# BMD_RevB_B2_TX.net
KiCad netlist of a schematic drawn in Altium Designer
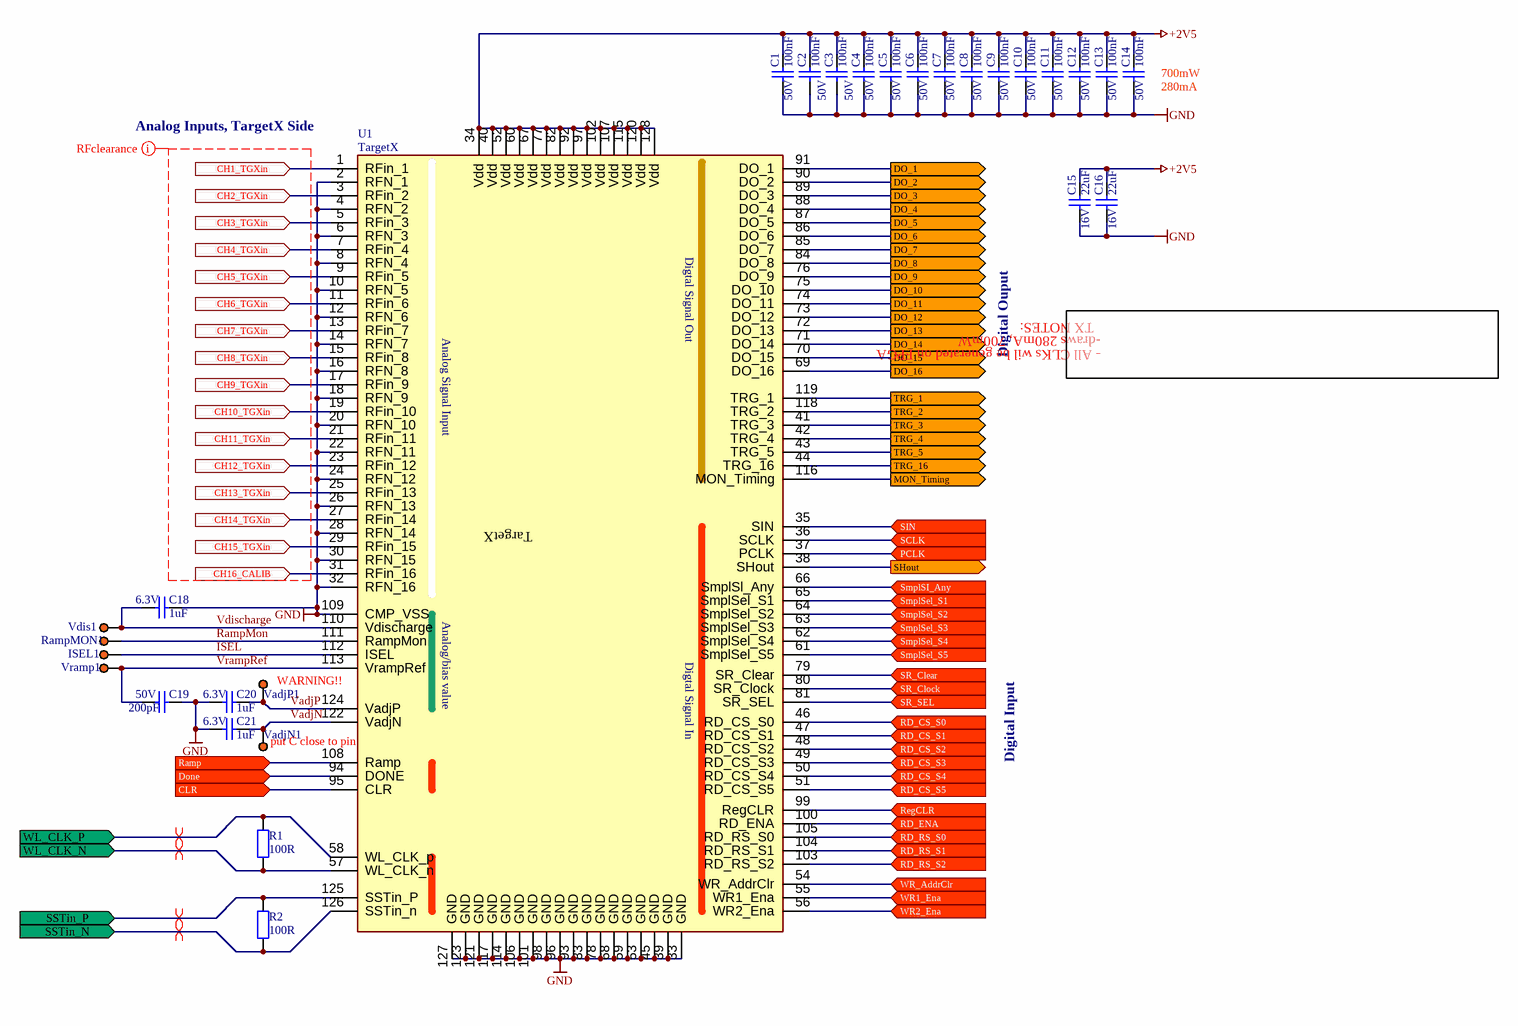
[diagram p0: BMD_RevB_B2_TX.SchDoc]

(export (version "E")
  (design (tool "Eeschema 10.0.6"))
  (components
    (comp (ref "C1")
      (value "100nF")
      (footprint "CC0402N1R")
      (description "0.10µF 50V Ceramic Capacitor X7R 0402")
      (fields (field (name "MANUFACTURER") "TDK") (field (name "VOLTAGE RATING") "50V"))
      (libsource (lib "BMD") (part "CAPCC0402_100N_50VX7R"))
    )
    (comp (ref "C2")
      (value "100nF")
      (footprint "CC0402N1R")
      (description "0.10µF 50V Ceramic Capacitor X7R 0402")
      (fields (field (name "MANUFACTURER") "TDK") (field (name "VOLTAGE RATING") "50V"))
      (libsource (lib "BMD") (part "CAPCC0402_100N_50VX7R"))
    )
    (comp (ref "C3")
      (value "100nF")
      (footprint "CC0402N1R")
      (description "0.10µF 50V Ceramic Capacitor X7R 0402")
      (fields (field (name "MANUFACTURER") "TDK") (field (name "VOLTAGE RATING") "50V"))
      (libsource (lib "BMD") (part "CAPCC0402_100N_50VX7R"))
    )
    (comp (ref "C4")
      (value "100nF")
      (footprint "CC0402N1R")
      (description "0.10µF 50V Ceramic Capacitor X7R 0402")
      (fields (field (name "MANUFACTURER") "TDK") (field (name "VOLTAGE RATING") "50V"))
      (libsource (lib "BMD") (part "CAPCC0402_100N_50VX7R"))
    )
    (comp (ref "C5")
      (value "100nF")
      (footprint "CC0402N1R")
      (description "0.10µF 50V Ceramic Capacitor X7R 0402")
      (fields (field (name "MANUFACTURER") "TDK") (field (name "VOLTAGE RATING") "50V"))
      (libsource (lib "BMD") (part "CAPCC0402_100N_50VX7R"))
    )
    (comp (ref "C6")
      (value "100nF")
      (footprint "CC0402N1R")
      (description "0.10µF 50V Ceramic Capacitor X7R 0402")
      (fields (field (name "MANUFACTURER") "TDK") (field (name "VOLTAGE RATING") "50V"))
      (libsource (lib "BMD") (part "CAPCC0402_100N_50VX7R"))
    )
    (comp (ref "C7")
      (value "100nF")
      (footprint "CC0402N1R")
      (description "0.10µF 50V Ceramic Capacitor X7R 0402")
      (fields (field (name "MANUFACTURER") "TDK") (field (name "VOLTAGE RATING") "50V"))
      (libsource (lib "BMD") (part "CAPCC0402_100N_50VX7R"))
    )
    (comp (ref "C8")
      (value "100nF")
      (footprint "CC0402N1R")
      (description "0.10µF 50V Ceramic Capacitor X7R 0402")
      (fields (field (name "MANUFACTURER") "TDK") (field (name "VOLTAGE RATING") "50V"))
      (libsource (lib "BMD") (part "CAPCC0402_100N_50VX7R"))
    )
    (comp (ref "C9")
      (value "100nF")
      (footprint "CC0402N1R")
      (description "0.10µF 50V Ceramic Capacitor X7R 0402")
      (fields (field (name "MANUFACTURER") "TDK") (field (name "VOLTAGE RATING") "50V"))
      (libsource (lib "BMD") (part "CAPCC0402_100N_50VX7R"))
    )
    (comp (ref "C10")
      (value "100nF")
      (footprint "CC0402N1R")
      (description "0.10µF 50V Ceramic Capacitor X7R 0402")
      (fields (field (name "MANUFACTURER") "TDK") (field (name "VOLTAGE RATING") "50V"))
      (libsource (lib "BMD") (part "CAPCC0402_100N_50VX7R"))
    )
    (comp (ref "C11")
      (value "100nF")
      (footprint "CC0402N1R")
      (description "0.10µF 50V Ceramic Capacitor X7R 0402")
      (fields (field (name "MANUFACTURER") "TDK") (field (name "VOLTAGE RATING") "50V"))
      (libsource (lib "BMD") (part "CAPCC0402_100N_50VX7R"))
    )
    (comp (ref "C12")
      (value "100nF")
      (footprint "CC0402N1R")
      (description "0.10µF 50V Ceramic Capacitor X7R 0402")
      (fields (field (name "MANUFACTURER") "TDK") (field (name "VOLTAGE RATING") "50V"))
      (libsource (lib "BMD") (part "CAPCC0402_100N_50VX7R"))
    )
    (comp (ref "C13")
      (value "100nF")
      (footprint "CC0402N1R")
      (description "0.10µF 50V Ceramic Capacitor X7R 0402")
      (fields (field (name "MANUFACTURER") "TDK") (field (name "VOLTAGE RATING") "50V"))
      (libsource (lib "BMD") (part "CAPCC0402_100N_50VX7R"))
    )
    (comp (ref "C14")
      (value "100nF")
      (footprint "CC0402N1R")
      (description "0.10µF 50V Ceramic Capacitor X7R 0402")
      (fields (field (name "MANUFACTURER") "TDK") (field (name "VOLTAGE RATING") "50V"))
      (libsource (lib "BMD") (part "CAPCC0402_100N_50VX7R"))
    )
    (comp (ref "C15")
      (value "22uF")
      (footprint "CC0805N1R")
      (description "22µF 16V Ceramic Capacitor X5R 0805")
      (fields (field (name "MANUFACTURER") "Murata") (field (name "VOLTAGE RATING") "16V"))
      (libsource (lib "BMD") (part "CAPCC0805_22U_16VX7R"))
    )
    (comp (ref "C16")
      (value "22uF")
      (footprint "CC0805N1R")
      (description "22µF 16V Ceramic Capacitor X5R 0805")
      (fields (field (name "MANUFACTURER") "Murata") (field (name "VOLTAGE RATING") "16V"))
      (libsource (lib "BMD") (part "CAPCC0805_22U_16VX7R"))
    )
    (comp (ref "C18")
      (value "1uF")
      (footprint "CC0402N1R")
      (description "1µF 6.3V Ceramic Capacitor X7R 0402")
      (fields (field (name "MANUFACTURER") "TDK") (field (name "VOLTAGE RATING") "6.3V"))
      (libsource (lib "BMD") (part "CAPCC0402_1.0U_50VX7R"))
    )
    (comp (ref "C19")
      (value "200pF")
      (footprint "CC0402N1R")
      (description "Capacitor chip ceramic 0402 50V NPO")
      (fields (field (name "MANUFACTURER") "Murata") (field (name "VOLTAGE RATING") "50V"))
      (libsource (lib "BMD") (part "CAPCC0402_200P_50VNP0"))
    )
    (comp (ref "C20")
      (value "1uF")
      (footprint "CC0402N1R")
      (description "1µF 6.3V Ceramic Capacitor X7R 0402")
      (fields (field (name "MANUFACTURER") "TDK") (field (name "VOLTAGE RATING") "6.3V"))
      (libsource (lib "BMD") (part "CAPCC0402_1.0U_50VX7R"))
    )
    (comp (ref "C21")
      (value "1uF")
      (footprint "CC0402N1R")
      (description "1µF 6.3V Ceramic Capacitor X7R 0402")
      (fields (field (name "MANUFACTURER") "TDK") (field (name "VOLTAGE RATING") "6.3V"))
      (libsource (lib "BMD") (part "CAPCC0402_1.0U_50VX7R"))
    )
    (comp (ref "ISEL1")
      (value "SP1.5S")
      (footprint "SP1.5SQ")
      (description "Wire solder pin 1.5mm")
      (libsource (lib "Connectors_Old") (part "SP1.5S"))
    )
    (comp (ref "R1")
      (value "100R")
      (footprint "RC0402N1R")
      (description "RES SMD 100 OHM 1% 1/10W 0402")
      (fields (field (name "MANUFACTURER") "Panasonic"))
      (libsource (lib "BMD") (part "RES0402-100R-1%100PPM"))
    )
    (comp (ref "R2")
      (value "100R")
      (footprint "RC0402N1R")
      (description "RES SMD 100 OHM 1% 1/10W 0402")
      (fields (field (name "MANUFACTURER") "Panasonic"))
      (libsource (lib "BMD") (part "RES0402-100R-1%100PPM"))
    )
    (comp (ref "RampMON1")
      (value "SP1.5S")
      (footprint "SP1.5SQ")
      (description "Wire solder pin 1.5mm")
      (libsource (lib "Connectors_Old") (part "SP1.5S"))
    )
    (comp (ref "U1")
      (value "TargetX")
      (footprint "TQFP128_MZA")
      (description "16-channel, 1GSPS Transient Waveform Recorder")
      (fields (field (name "MANUFACTURER") "UHM_IDL"))
      (libsource (lib "IDlab") (part "DIGITZ_TargetX"))
    )
    (comp (ref "VadjN1")
      (value "SP1.5S")
      (footprint "SP1.5SQ")
      (description "Wire solder pin 1.5mm")
      (libsource (lib "Connectors_Old") (part "SP1.5S"))
    )
    (comp (ref "VadjP1")
      (value "SP1.5S")
      (footprint "SP1.5SQ")
      (description "Wire solder pin 1.5mm")
      (libsource (lib "Connectors_Old") (part "SP1.5S"))
    )
    (comp (ref "Vdis1")
      (value "SP1.5S")
      (footprint "SP1.5SQ")
      (description "Wire solder pin 1.5mm")
      (libsource (lib "Connectors_Old") (part "SP1.5S"))
    )
    (comp (ref "Vramp1")
      (value "SP1.5S")
      (footprint "SP1.5SQ")
      (description "Wire solder pin 1.5mm")
      (libsource (lib "Connectors_Old") (part "SP1.5S"))
    )
  )
  (nets
    (net (code "1") (name "+2V5") (class "Default")
      (node (ref "C1") (pin "2") (pinfunction "2_2") (pintype "passive"))
      (node (ref "C10") (pin "2") (pinfunction "2_2") (pintype "passive"))
      (node (ref "C11") (pin "2") (pinfunction "2_2") (pintype "passive"))
      (node (ref "C12") (pin "2") (pinfunction "2_2") (pintype "passive"))
      (node (ref "C13") (pin "2") (pinfunction "2_2") (pintype "passive"))
      (node (ref "C14") (pin "2") (pinfunction "2_2") (pintype "passive"))
      (node (ref "C15") (pin "2") (pinfunction "2_2") (pintype "passive"))
      (node (ref "C16") (pin "2") (pinfunction "2_2") (pintype "passive"))
      (node (ref "C2") (pin "2") (pinfunction "2_2") (pintype "passive"))
      (node (ref "C3") (pin "2") (pinfunction "2_2") (pintype "passive"))
      (node (ref "C4") (pin "2") (pinfunction "2_2") (pintype "passive"))
      (node (ref "C5") (pin "2") (pinfunction "2_2") (pintype "passive"))
      (node (ref "C6") (pin "2") (pinfunction "2_2") (pintype "passive"))
      (node (ref "C7") (pin "2") (pinfunction "2_2") (pintype "passive"))
      (node (ref "C8") (pin "2") (pinfunction "2_2") (pintype "passive"))
      (node (ref "C9") (pin "2") (pinfunction "2_2") (pintype "passive"))
      (node (ref "U1") (pin "102") (pinfunction "Vdd_102") (pintype "passive"))
      (node (ref "U1") (pin "107") (pinfunction "Vdd_107") (pintype "passive"))
      (node (ref "U1") (pin "115") (pinfunction "Vdd_115") (pintype "passive"))
      (node (ref "U1") (pin "120") (pinfunction "Vdd_120") (pintype "passive"))
      (node (ref "U1") (pin "128") (pinfunction "Vdd_128") (pintype "passive"))
      (node (ref "U1") (pin "34") (pinfunction "Vdd_34") (pintype "passive"))
      (node (ref "U1") (pin "40") (pinfunction "Vdd_40") (pintype "passive"))
      (node (ref "U1") (pin "52") (pinfunction "Vdd_52") (pintype "passive"))
      (node (ref "U1") (pin "60") (pinfunction "Vdd_60") (pintype "passive"))
      (node (ref "U1") (pin "67") (pinfunction "Vdd_67") (pintype "passive"))
      (node (ref "U1") (pin "77") (pinfunction "Vdd_77") (pintype "passive"))
      (node (ref "U1") (pin "82") (pinfunction "Vdd_82") (pintype "passive"))
      (node (ref "U1") (pin "92") (pinfunction "Vdd_92") (pintype "passive"))
      (node (ref "U1") (pin "97") (pinfunction "Vdd_97") (pintype "passive"))
    )
    (net (code "2") (name "/CH1_TGXin") (class "Default")
      (node (ref "U1") (pin "1") (pinfunction "RFin_1_1") (pintype "passive"))
    )
    (net (code "3") (name "/CH2_TGXin") (class "Default")
      (node (ref "U1") (pin "3") (pinfunction "RFin_2_3") (pintype "passive"))
    )
    (net (code "4") (name "/CH3_TGXin") (class "Default")
      (node (ref "U1") (pin "5") (pinfunction "RFin_3_5") (pintype "passive"))
    )
    (net (code "5") (name "/CH4_TGXin") (class "Default")
      (node (ref "U1") (pin "7") (pinfunction "RFin_4_7") (pintype "passive"))
    )
    (net (code "6") (name "/CH5_TGXin") (class "Default")
      (node (ref "U1") (pin "9") (pinfunction "RFin_5_9") (pintype "passive"))
    )
    (net (code "7") (name "/CH6_TGXin") (class "Default")
      (node (ref "U1") (pin "11") (pinfunction "RFin_6_11") (pintype "passive"))
    )
    (net (code "8") (name "/CH7_TGXin") (class "Default")
      (node (ref "U1") (pin "13") (pinfunction "RFin_7_13") (pintype "passive"))
    )
    (net (code "9") (name "/CH8_TGXin") (class "Default")
      (node (ref "U1") (pin "15") (pinfunction "RFin_8_15") (pintype "passive"))
    )
    (net (code "10") (name "/CH9_TGXin") (class "Default")
      (node (ref "U1") (pin "17") (pinfunction "RFin_9_17") (pintype "passive"))
    )
    (net (code "11") (name "/CH10_TGXin") (class "Default")
      (node (ref "U1") (pin "19") (pinfunction "RFin_10_19") (pintype "passive"))
    )
    (net (code "12") (name "/CH11_TGXin") (class "Default")
      (node (ref "U1") (pin "21") (pinfunction "RFin_11_21") (pintype "passive"))
    )
    (net (code "13") (name "/CH12_TGXin") (class "Default")
      (node (ref "U1") (pin "23") (pinfunction "RFin_12_23") (pintype "passive"))
    )
    (net (code "14") (name "/CH13_TGXin") (class "Default")
      (node (ref "U1") (pin "25") (pinfunction "RFin_13_25") (pintype "passive"))
    )
    (net (code "15") (name "/CH14_TGXin") (class "Default")
      (node (ref "U1") (pin "27") (pinfunction "RFin_14_27") (pintype "passive"))
    )
    (net (code "16") (name "/CH15_TGXin") (class "Default")
      (node (ref "U1") (pin "29") (pinfunction "RFin_15_29") (pintype "passive"))
    )
    (net (code "17") (name "/CH16_CALIB") (class "Default")
      (node (ref "U1") (pin "31") (pinfunction "RFin_16_31") (pintype "passive"))
    )
    (net (code "18") (name "/CLR") (class "Default")
      (node (ref "U1") (pin "95") (pinfunction "CLR_95") (pintype "passive"))
    )
    (net (code "19") (name "/DO_1") (class "Default")
      (node (ref "U1") (pin "91") (pinfunction "DO_1_91") (pintype "passive"))
    )
    (net (code "20") (name "/DO_2") (class "Default")
      (node (ref "U1") (pin "90") (pinfunction "DO_2_90") (pintype "passive"))
    )
    (net (code "21") (name "/DO_3") (class "Default")
      (node (ref "U1") (pin "89") (pinfunction "DO_3_89") (pintype "passive"))
    )
    (net (code "22") (name "/DO_4") (class "Default")
      (node (ref "U1") (pin "88") (pinfunction "DO_4_88") (pintype "passive"))
    )
    (net (code "23") (name "/DO_5") (class "Default")
      (node (ref "U1") (pin "87") (pinfunction "DO_5_87") (pintype "passive"))
    )
    (net (code "24") (name "/DO_6") (class "Default")
      (node (ref "U1") (pin "86") (pinfunction "DO_6_86") (pintype "passive"))
    )
    (net (code "25") (name "/DO_7") (class "Default")
      (node (ref "U1") (pin "85") (pinfunction "DO_7_85") (pintype "passive"))
    )
    (net (code "26") (name "/DO_8") (class "Default")
      (node (ref "U1") (pin "84") (pinfunction "DO_8_84") (pintype "passive"))
    )
    (net (code "27") (name "/DO_9") (class "Default")
      (node (ref "U1") (pin "76") (pinfunction "DO_9_76") (pintype "passive"))
    )
    (net (code "28") (name "/DO_10") (class "Default")
      (node (ref "U1") (pin "75") (pinfunction "DO_10_75") (pintype "passive"))
    )
    (net (code "29") (name "/DO_11") (class "Default")
      (node (ref "U1") (pin "74") (pinfunction "DO_11_74") (pintype "passive"))
    )
    (net (code "30") (name "/DO_12") (class "Default")
      (node (ref "U1") (pin "73") (pinfunction "DO_12_73") (pintype "passive"))
    )
    (net (code "31") (name "/DO_13") (class "Default")
      (node (ref "U1") (pin "72") (pinfunction "DO_13_72") (pintype "passive"))
    )
    (net (code "32") (name "/DO_14") (class "Default")
      (node (ref "U1") (pin "71") (pinfunction "DO_14_71") (pintype "passive"))
    )
    (net (code "33") (name "/DO_15") (class "Default")
      (node (ref "U1") (pin "70") (pinfunction "DO_15_70") (pintype "passive"))
    )
    (net (code "34") (name "/DO_16") (class "Default")
      (node (ref "U1") (pin "69") (pinfunction "DO_16_69") (pintype "passive"))
    )
    (net (code "35") (name "/Done") (class "Default")
      (node (ref "U1") (pin "94") (pinfunction "DONE_94") (pintype "passive"))
    )
    (net (code "36") (name "/ISEL") (class "Default")
      (node (ref "ISEL1") (pin "1") (pinfunction "1_1") (pintype "passive"))
      (node (ref "U1") (pin "112") (pinfunction "ISEL_112") (pintype "passive"))
    )
    (net (code "37") (name "/MON_Timing") (class "Default")
      (node (ref "U1") (pin "116") (pinfunction "MON_Timing_116") (pintype "passive"))
    )
    (net (code "38") (name "/PCLK") (class "Default")
      (node (ref "U1") (pin "37") (pinfunction "PCLK_37") (pintype "passive"))
    )
    (net (code "39") (name "/RD_CS_S0") (class "Default")
      (node (ref "U1") (pin "46") (pinfunction "RD_CS_S0_46") (pintype "passive"))
    )
    (net (code "40") (name "/RD_CS_S1") (class "Default")
      (node (ref "U1") (pin "47") (pinfunction "RD_CS_S1_47") (pintype "passive"))
    )
    (net (code "41") (name "/RD_CS_S2") (class "Default")
      (node (ref "U1") (pin "48") (pinfunction "RD_CS_S2_48") (pintype "passive"))
    )
    (net (code "42") (name "/RD_CS_S3") (class "Default")
      (node (ref "U1") (pin "49") (pinfunction "RD_CS_S3_49") (pintype "passive"))
    )
    (net (code "43") (name "/RD_CS_S4") (class "Default")
      (node (ref "U1") (pin "50") (pinfunction "RD_CS_S4_50") (pintype "passive"))
    )
    (net (code "44") (name "/RD_CS_S5") (class "Default")
      (node (ref "U1") (pin "51") (pinfunction "RD_CS_S5_51") (pintype "passive"))
    )
    (net (code "45") (name "/RD_ENA") (class "Default")
      (node (ref "U1") (pin "100") (pinfunction "RD_ENA_100") (pintype "passive"))
    )
    (net (code "46") (name "/RD_RS_S0") (class "Default")
      (node (ref "U1") (pin "105") (pinfunction "RD_RS_S0_105") (pintype "passive"))
    )
    (net (code "47") (name "/RD_RS_S1") (class "Default")
      (node (ref "U1") (pin "104") (pinfunction "RD_RS_S1_104") (pintype "passive"))
    )
    (net (code "48") (name "/RD_RS_S2") (class "Default")
      (node (ref "U1") (pin "103") (pinfunction "RD_RS_S2_103") (pintype "passive"))
    )
    (net (code "49") (name "/Ramp") (class "Default")
      (node (ref "U1") (pin "108") (pinfunction "Ramp_108") (pintype "passive"))
    )
    (net (code "50") (name "/RampMon") (class "Default")
      (node (ref "RampMON1") (pin "1") (pinfunction "1_1") (pintype "passive"))
      (node (ref "U1") (pin "111") (pinfunction "RampMon_111") (pintype "passive"))
    )
    (net (code "51") (name "/RegCLR") (class "Default")
      (node (ref "U1") (pin "99") (pinfunction "RegCLR_99") (pintype "passive"))
    )
    (net (code "52") (name "/SCLK") (class "Default")
      (node (ref "U1") (pin "36") (pinfunction "SCLK_36") (pintype "passive"))
    )
    (net (code "53") (name "/SHout") (class "Default")
      (node (ref "U1") (pin "38") (pinfunction "SHout_38") (pintype "passive"))
    )
    (net (code "54") (name "/SIN") (class "Default")
      (node (ref "U1") (pin "35") (pinfunction "SIN_35") (pintype "passive"))
    )
    (net (code "55") (name "/SR_Clear") (class "Default")
      (node (ref "U1") (pin "79") (pinfunction "SR_Clear_79") (pintype "passive"))
    )
    (net (code "56") (name "/SR_Clock") (class "Default")
      (node (ref "U1") (pin "80") (pinfunction "SR_Clock_80") (pintype "passive"))
    )
    (net (code "57") (name "/SR_SEL") (class "Default")
      (node (ref "U1") (pin "81") (pinfunction "SR_SEL_81") (pintype "passive"))
    )
    (net (code "58") (name "/SSTin_N") (class "Default")
      (node (ref "R2") (pin "1") (pinfunction "1_1") (pintype "passive"))
      (node (ref "U1") (pin "126") (pinfunction "SSTin_n_126") (pintype "passive"))
    )
    (net (code "59") (name "/SSTin_P") (class "Default")
      (node (ref "R2") (pin "2") (pinfunction "2_2") (pintype "passive"))
      (node (ref "U1") (pin "125") (pinfunction "SSTin_P_125") (pintype "passive"))
    )
    (net (code "60") (name "/SmplSI_Any") (class "Default")
      (node (ref "U1") (pin "66") (pinfunction "SmplSl_Any_66") (pintype "passive"))
    )
    (net (code "61") (name "/SmplSel_S1") (class "Default")
      (node (ref "U1") (pin "65") (pinfunction "SmplSel_S1_65") (pintype "passive"))
    )
    (net (code "62") (name "/SmplSel_S2") (class "Default")
      (node (ref "U1") (pin "64") (pinfunction "SmplSel_S2_64") (pintype "passive"))
    )
    (net (code "63") (name "/SmplSel_S3") (class "Default")
      (node (ref "U1") (pin "63") (pinfunction "SmplSel_S3_63") (pintype "passive"))
    )
    (net (code "64") (name "/SmplSel_S4") (class "Default")
      (node (ref "U1") (pin "62") (pinfunction "SmplSel_S4_62") (pintype "passive"))
    )
    (net (code "65") (name "/SmplSel_S5") (class "Default")
      (node (ref "U1") (pin "61") (pinfunction "SmplSel_S5_61") (pintype "passive"))
    )
    (net (code "66") (name "/TRG_1") (class "Default")
      (node (ref "U1") (pin "119") (pinfunction "TRG_1_119") (pintype "passive"))
    )
    (net (code "67") (name "/TRG_2") (class "Default")
      (node (ref "U1") (pin "118") (pinfunction "TRG_2_118") (pintype "passive"))
    )
    (net (code "68") (name "/TRG_3") (class "Default")
      (node (ref "U1") (pin "41") (pinfunction "TRG_3_41") (pintype "passive"))
    )
    (net (code "69") (name "/TRG_4") (class "Default")
      (node (ref "U1") (pin "42") (pinfunction "TRG_4_42") (pintype "passive"))
    )
    (net (code "70") (name "/TRG_5") (class "Default")
      (node (ref "U1") (pin "43") (pinfunction "TRG_5_43") (pintype "passive"))
    )
    (net (code "71") (name "/TRG_16") (class "Default")
      (node (ref "U1") (pin "44") (pinfunction "TRG_16_44") (pintype "passive"))
    )
    (net (code "72") (name "/VadjN") (class "Default")
      (node (ref "C21") (pin "2") (pinfunction "2_2") (pintype "passive"))
      (node (ref "U1") (pin "122") (pinfunction "VadjN_122") (pintype "passive"))
      (node (ref "VadjN1") (pin "1") (pinfunction "1_1") (pintype "passive"))
    )
    (net (code "73") (name "/VadjP") (class "Default")
      (node (ref "C20") (pin "2") (pinfunction "2_2") (pintype "passive"))
      (node (ref "U1") (pin "124") (pinfunction "VadjP_124") (pintype "passive"))
      (node (ref "VadjP1") (pin "1") (pinfunction "1_1") (pintype "passive"))
    )
    (net (code "74") (name "/Vdischarge") (class "Default")
      (node (ref "C18") (pin "1") (pinfunction "1_1") (pintype "passive"))
      (node (ref "U1") (pin "110") (pinfunction "Vdischarge_110") (pintype "passive"))
      (node (ref "Vdis1") (pin "1") (pinfunction "1_1") (pintype "passive"))
    )
    (net (code "75") (name "/VrampRef") (class "Default")
      (node (ref "C19") (pin "2") (pinfunction "2_2") (pintype "passive"))
      (node (ref "U1") (pin "113") (pinfunction "VrampRef_113") (pintype "passive"))
      (node (ref "Vramp1") (pin "1") (pinfunction "1_1") (pintype "passive"))
    )
    (net (code "76") (name "/WL_CLK_N") (class "Default")
      (node (ref "R1") (pin "1") (pinfunction "1_1") (pintype "passive"))
      (node (ref "U1") (pin "57") (pinfunction "WL_CLK_n_57") (pintype "passive"))
    )
    (net (code "77") (name "/WL_CLK_P") (class "Default")
      (node (ref "R1") (pin "2") (pinfunction "2_2") (pintype "passive"))
      (node (ref "U1") (pin "58") (pinfunction "WL_CLK_p_58") (pintype "passive"))
    )
    (net (code "78") (name "/WR1_Ena") (class "Default")
      (node (ref "U1") (pin "55") (pinfunction "WR1_Ena_55") (pintype "passive"))
    )
    (net (code "79") (name "/WR2_Ena") (class "Default")
      (node (ref "U1") (pin "56") (pinfunction "WR2_Ena_56") (pintype "passive"))
    )
    (net (code "80") (name "/WR_AddrClr") (class "Default")
      (node (ref "U1") (pin "54") (pinfunction "WR_AddrClr_54") (pintype "passive"))
    )
    (net (code "81") (name "GND") (class "Default")
      (node (ref "C1") (pin "1") (pinfunction "1_1") (pintype "passive"))
      (node (ref "C10") (pin "1") (pinfunction "1_1") (pintype "passive"))
      (node (ref "C11") (pin "1") (pinfunction "1_1") (pintype "passive"))
      (node (ref "C12") (pin "1") (pinfunction "1_1") (pintype "passive"))
      (node (ref "C13") (pin "1") (pinfunction "1_1") (pintype "passive"))
      (node (ref "C14") (pin "1") (pinfunction "1_1") (pintype "passive"))
      (node (ref "C15") (pin "1") (pinfunction "1_1") (pintype "passive"))
      (node (ref "C16") (pin "1") (pinfunction "1_1") (pintype "passive"))
      (node (ref "C18") (pin "2") (pinfunction "2_2") (pintype "passive"))
      (node (ref "C19") (pin "1") (pinfunction "1_1") (pintype "passive"))
      (node (ref "C2") (pin "1") (pinfunction "1_1") (pintype "passive"))
      (node (ref "C20") (pin "1") (pinfunction "1_1") (pintype "passive"))
      (node (ref "C21") (pin "1") (pinfunction "1_1") (pintype "passive"))
      (node (ref "C3") (pin "1") (pinfunction "1_1") (pintype "passive"))
      (node (ref "C4") (pin "1") (pinfunction "1_1") (pintype "passive"))
      (node (ref "C5") (pin "1") (pinfunction "1_1") (pintype "passive"))
      (node (ref "C6") (pin "1") (pinfunction "1_1") (pintype "passive"))
      (node (ref "C7") (pin "1") (pinfunction "1_1") (pintype "passive"))
      (node (ref "C8") (pin "1") (pinfunction "1_1") (pintype "passive"))
      (node (ref "C9") (pin "1") (pinfunction "1_1") (pintype "passive"))
      (node (ref "U1") (pin "10") (pinfunction "RFN_5_10") (pintype "passive"))
      (node (ref "U1") (pin "101") (pinfunction "GND_101") (pintype "passive"))
      (node (ref "U1") (pin "106") (pinfunction "GND_106") (pintype "passive"))
      (node (ref "U1") (pin "109") (pinfunction "CMP_VSS_109") (pintype "passive"))
      (node (ref "U1") (pin "114") (pinfunction "GND_114") (pintype "passive"))
      (node (ref "U1") (pin "117") (pinfunction "GND_117") (pintype "passive"))
      (node (ref "U1") (pin "12") (pinfunction "RFN_6_12") (pintype "passive"))
      (node (ref "U1") (pin "121") (pinfunction "GND_121") (pintype "passive"))
      (node (ref "U1") (pin "123") (pinfunction "GND_123") (pintype "passive"))
      (node (ref "U1") (pin "127") (pinfunction "GND_127") (pintype "passive"))
      (node (ref "U1") (pin "14") (pinfunction "RFN_7_14") (pintype "passive"))
      (node (ref "U1") (pin "16") (pinfunction "RFN_8_16") (pintype "passive"))
      (node (ref "U1") (pin "18") (pinfunction "RFN_9_18") (pintype "passive"))
      (node (ref "U1") (pin "2") (pinfunction "RFN_1_2") (pintype "passive"))
      (node (ref "U1") (pin "20") (pinfunction "RFN_10_20") (pintype "passive"))
      (node (ref "U1") (pin "22") (pinfunction "RFN_11_22") (pintype "passive"))
      (node (ref "U1") (pin "24") (pinfunction "RFN_12_24") (pintype "passive"))
      (node (ref "U1") (pin "26") (pinfunction "RFN_13_26") (pintype "passive"))
      (node (ref "U1") (pin "28") (pinfunction "RFN_14_28") (pintype "passive"))
      (node (ref "U1") (pin "30") (pinfunction "RFN_15_30") (pintype "passive"))
      (node (ref "U1") (pin "32") (pinfunction "RFN_16_32") (pintype "passive"))
      (node (ref "U1") (pin "33") (pinfunction "GND_33") (pintype "passive"))
      (node (ref "U1") (pin "39") (pinfunction "GND_39") (pintype "passive"))
      (node (ref "U1") (pin "4") (pinfunction "RFN_2_4") (pintype "passive"))
      (node (ref "U1") (pin "45") (pinfunction "GND_45") (pintype "passive"))
      (node (ref "U1") (pin "53") (pinfunction "GND_53") (pintype "passive"))
      (node (ref "U1") (pin "59") (pinfunction "GND_59") (pintype "passive"))
      (node (ref "U1") (pin "6") (pinfunction "RFN_3_6") (pintype "passive"))
      (node (ref "U1") (pin "68") (pinfunction "GND_68") (pintype "passive"))
      (node (ref "U1") (pin "78") (pinfunction "GND_78") (pintype "passive"))
      (node (ref "U1") (pin "8") (pinfunction "RFN_4_8") (pintype "passive"))
      (node (ref "U1") (pin "83") (pinfunction "GND_83") (pintype "passive"))
      (node (ref "U1") (pin "93") (pinfunction "GND_93") (pintype "passive"))
      (node (ref "U1") (pin "96") (pinfunction "GND_96") (pintype "passive"))
      (node (ref "U1") (pin "98") (pinfunction "GND_98") (pintype "passive"))
    )
  )
)
